# MotionerController.net
KiCad netlist of a schematic drawn in EAGLE
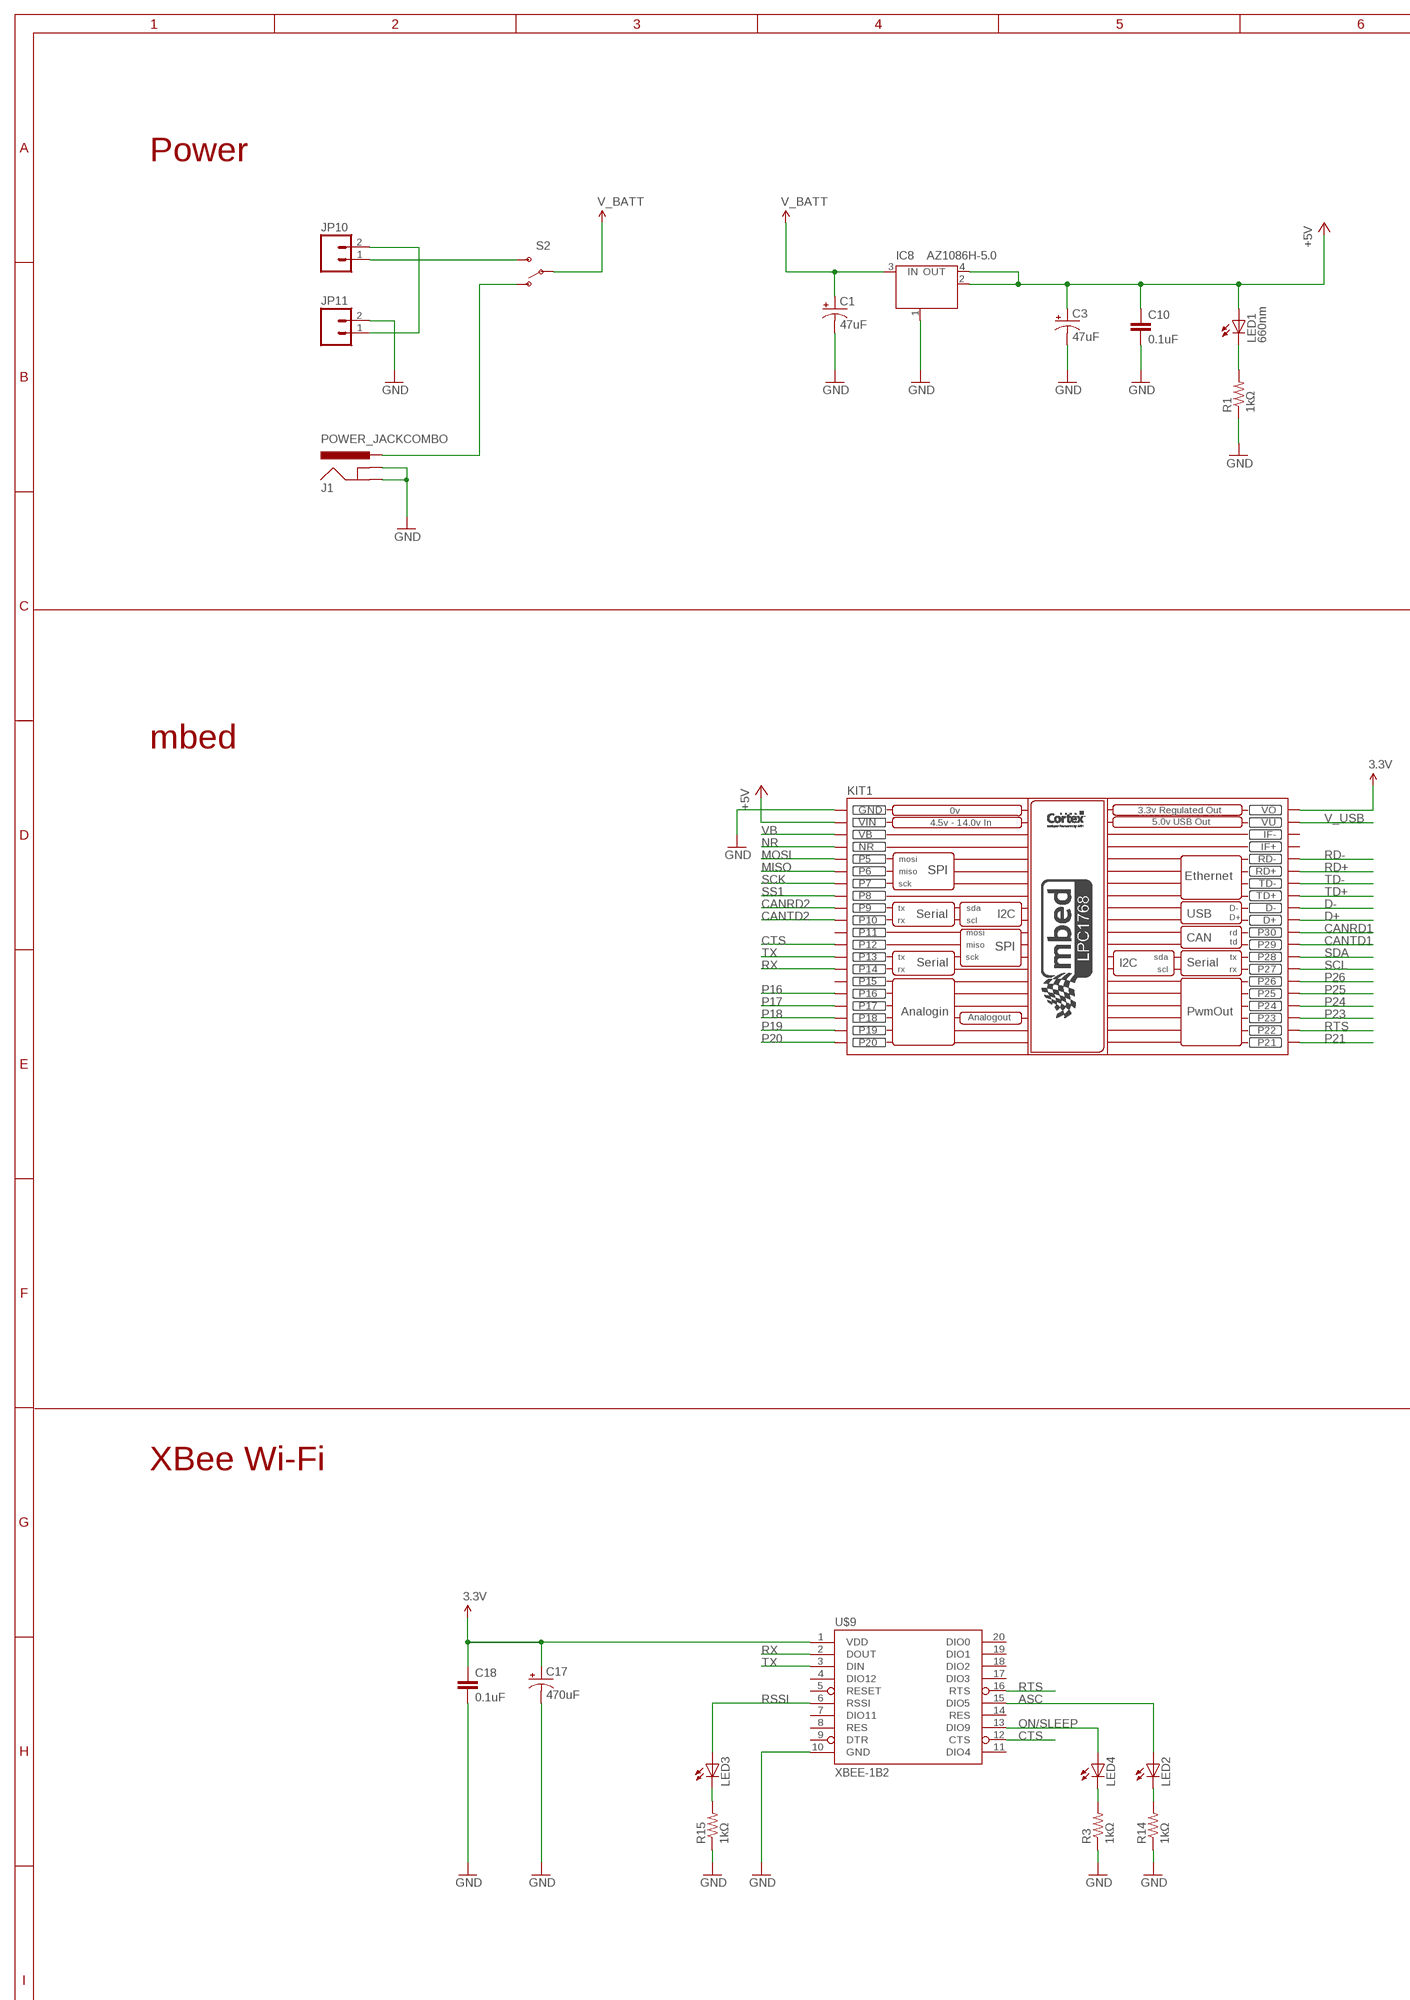
[diagram p0: schematic, sheet 1, part 1 of 2]
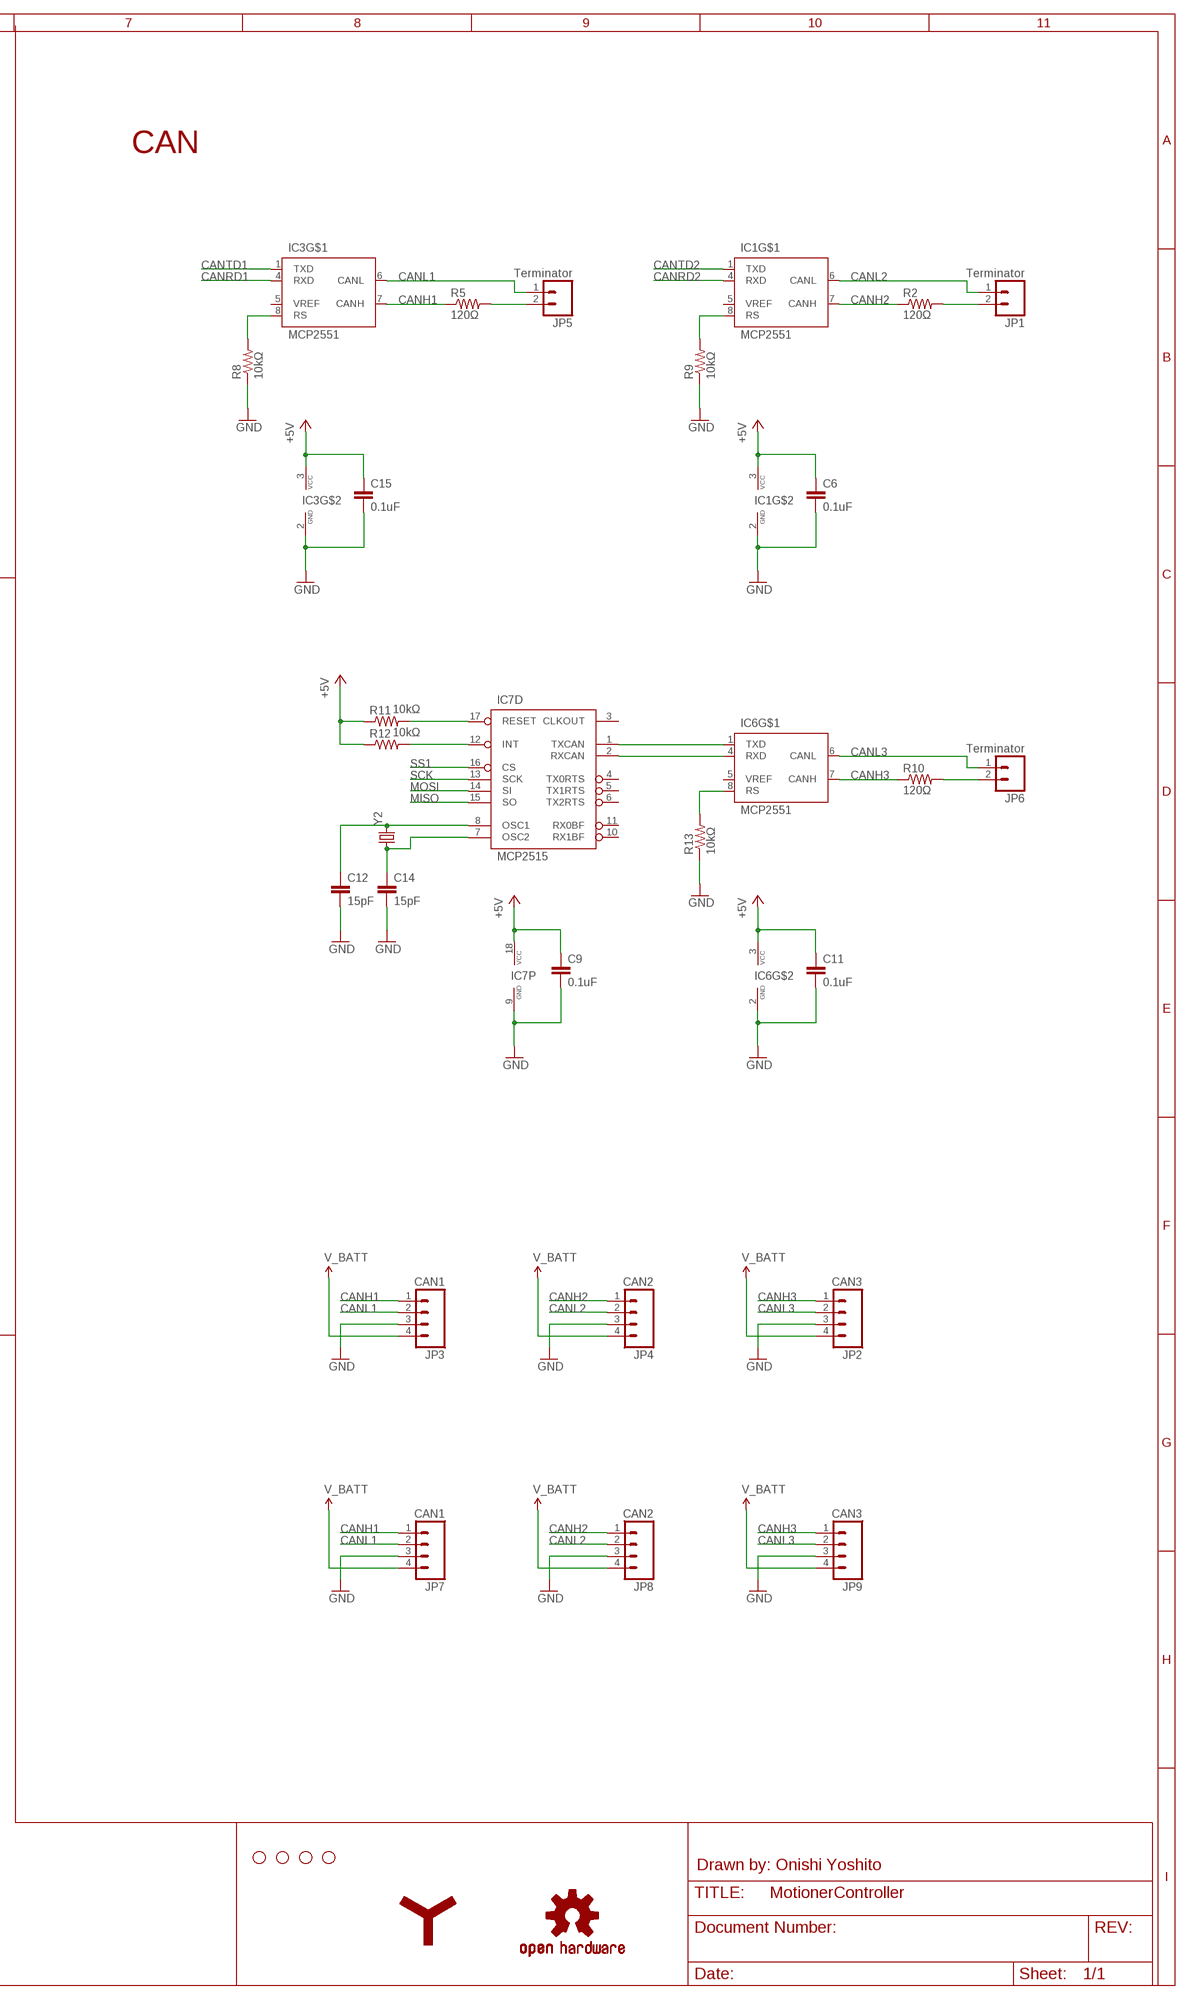
[diagram p1: schematic, sheet 1, part 2 of 2]

(export (version "E")
  (design (tool "Eeschema 10.0.6"))
  (components
    (comp (ref "C1")
      (value "47uF")
      (footprint "eagle-import:PANASONIC_D")
      (libsource (lib "eagle-import") (part "CAP_POLD"))
    )
    (comp (ref "C3")
      (value "47uF")
      (footprint "eagle-import:PANASONIC_D")
      (libsource (lib "eagle-import") (part "CAP_POLD"))
    )
    (comp (ref "C6")
      (value "0.1uF")
      (footprint "eagle-import:0603-CAP")
      (libsource (lib "eagle-import") (part "CAP0603-CAP"))
    )
    (comp (ref "C9")
      (value "0.1uF")
      (footprint "eagle-import:0603-CAP")
      (libsource (lib "eagle-import") (part "CAP0603-CAP"))
    )
    (comp (ref "C10")
      (value "0.1uF")
      (footprint "eagle-import:0603-CAP")
      (libsource (lib "eagle-import") (part "CAP0603-CAP"))
    )
    (comp (ref "C11")
      (value "0.1uF")
      (footprint "eagle-import:0603-CAP")
      (libsource (lib "eagle-import") (part "CAP0603-CAP"))
    )
    (comp (ref "C12")
      (value "15pF")
      (footprint "eagle-import:0603-CAP")
      (libsource (lib "eagle-import") (part "CAP0603-CAP"))
    )
    (comp (ref "C14")
      (value "15pF")
      (footprint "eagle-import:0603-CAP")
      (libsource (lib "eagle-import") (part "CAP0603-CAP"))
    )
    (comp (ref "C15")
      (value "0.1uF")
      (footprint "eagle-import:0603-CAP")
      (libsource (lib "eagle-import") (part "CAP0603-CAP"))
    )
    (comp (ref "C17")
      (value "470uF")
      (footprint "eagle-import:PANASONIC_G")
      (libsource (lib "eagle-import") (part "CAP_POLG"))
    )
    (comp (ref "C18")
      (value "0.1uF")
      (footprint "eagle-import:0603-CAP")
      (libsource (lib "eagle-import") (part "CAP0603-CAP"))
    )
    (comp (ref "IC1")
      (value "MCP2551")
      (footprint "eagle-import:SO08")
      (libsource (lib "eagle-import") (part "MCP2551SO8"))
    )
    (comp (ref "IC3")
      (value "MCP2551")
      (footprint "eagle-import:SO08")
      (libsource (lib "eagle-import") (part "MCP2551SO8"))
    )
    (comp (ref "IC6")
      (value "MCP2551")
      (footprint "eagle-import:SO08")
      (libsource (lib "eagle-import") (part "MCP2551SO8"))
    )
    (comp (ref "IC7")
      (value "MCP2515")
      (footprint "eagle-import:SO-18W")
      (libsource (lib "eagle-import") (part "MCP2515SO"))
    )
    (comp (ref "IC8")
      (value "AZ1086H-5.0")
      (footprint "eagle-import:SOT223")
      (libsource (lib "eagle-import") (part "MC33269ST-3.3T3"))
    )
    (comp (ref "J1")
      (value "POWER_JACKCOMBO")
      (footprint "eagle-import:POWER_JACK_COMBO")
      (libsource (lib "eagle-import") (part "POWER_JACKCOMBO"))
    )
    (comp (ref "JP1")
      (value "Terminator")
      (footprint "eagle-import:1X02")
      (libsource (lib "eagle-import") (part "M02PTH"))
    )
    (comp (ref "JP2")
      (value "CAN3")
      (footprint "eagle-import:JST-4-PTH")
      (libsource (lib "eagle-import") (part "M04JST-PTH"))
    )
    (comp (ref "JP3")
      (value "CAN1")
      (footprint "eagle-import:JST-4-PTH")
      (libsource (lib "eagle-import") (part "M04JST-PTH"))
    )
    (comp (ref "JP4")
      (value "CAN2")
      (footprint "eagle-import:JST-4-PTH")
      (libsource (lib "eagle-import") (part "M04JST-PTH"))
    )
    (comp (ref "JP5")
      (value "Terminator")
      (footprint "eagle-import:1X02")
      (libsource (lib "eagle-import") (part "M02PTH"))
    )
    (comp (ref "JP6")
      (value "Terminator")
      (footprint "eagle-import:1X02")
      (libsource (lib "eagle-import") (part "M02PTH"))
    )
    (comp (ref "JP7")
      (value "CAN1")
      (footprint "eagle-import:JST-4-PTH")
      (libsource (lib "eagle-import") (part "M04JST-PTH"))
    )
    (comp (ref "JP8")
      (value "CAN2")
      (footprint "eagle-import:JST-4-PTH")
      (libsource (lib "eagle-import") (part "M04JST-PTH"))
    )
    (comp (ref "JP9")
      (value "CAN3")
      (footprint "eagle-import:JST-4-PTH")
      (libsource (lib "eagle-import") (part "M04JST-PTH"))
    )
    (comp (ref "JP10")
      (value "M02JST-PTH-2")
      (footprint "eagle-import:JST-2-PTH")
      (libsource (lib "eagle-import") (part "M02JST-PTH-2"))
    )
    (comp (ref "JP11")
      (value "M02JST-PTH-2")
      (footprint "eagle-import:JST-2-PTH")
      (libsource (lib "eagle-import") (part "M02JST-PTH-2"))
    )
    (comp (ref "JP12")
      (value "STAND-OFF")
      (footprint "eagle-import:STAND-OFF")
      (libsource (lib "eagle-import") (part "STAND-OFF"))
    )
    (comp (ref "JP13")
      (value "STAND-OFF")
      (footprint "eagle-import:STAND-OFF")
      (libsource (lib "eagle-import") (part "STAND-OFF"))
    )
    (comp (ref "JP15")
      (value "STAND-OFF")
      (footprint "eagle-import:STAND-OFF")
      (libsource (lib "eagle-import") (part "STAND-OFF"))
    )
    (comp (ref "JP16")
      (value "STAND-OFF")
      (footprint "eagle-import:STAND-OFF")
      (libsource (lib "eagle-import") (part "STAND-OFF"))
    )
    (comp (ref "KIT1")
      (value "MBED_NXP_LPC1768")
      (footprint "eagle-import:MBED-KIT")
      (libsource (lib "eagle-import") (part "MBED_NXP_LPC1768"))
    )
    (comp (ref "LED1")
      (value "660nm")
      (footprint "eagle-import:LED-0603")
      (libsource (lib "eagle-import") (part "LED0603"))
    )
    (comp (ref "LED2")
      (value "LED0603")
      (footprint "eagle-import:LED-0603")
      (libsource (lib "eagle-import") (part "LED0603"))
    )
    (comp (ref "LED3")
      (value "LED0603")
      (footprint "eagle-import:LED-0603")
      (libsource (lib "eagle-import") (part "LED0603"))
    )
    (comp (ref "LED4")
      (value "LED0603")
      (footprint "eagle-import:LED-0603")
      (libsource (lib "eagle-import") (part "LED0603"))
    )
    (comp (ref "R1")
      (value "1kΩ")
      (footprint "eagle-import:0603-RES")
      (libsource (lib "eagle-import") (part "RESISTOR0603-RES"))
    )
    (comp (ref "R2")
      (value "120Ω")
      (footprint "eagle-import:0603-RES")
      (libsource (lib "eagle-import") (part "RESISTOR0603-RES"))
    )
    (comp (ref "R3")
      (value "1kΩ")
      (footprint "eagle-import:0603-RES")
      (libsource (lib "eagle-import") (part "RESISTOR0603-RES"))
    )
    (comp (ref "R5")
      (value "120Ω")
      (footprint "eagle-import:0603-RES")
      (libsource (lib "eagle-import") (part "RESISTOR0603-RES"))
    )
    (comp (ref "R8")
      (value "10kΩ")
      (footprint "eagle-import:0603-RES")
      (libsource (lib "eagle-import") (part "RESISTOR0603-RES"))
    )
    (comp (ref "R9")
      (value "10kΩ")
      (footprint "eagle-import:0603-RES")
      (libsource (lib "eagle-import") (part "RESISTOR0603-RES"))
    )
    (comp (ref "R10")
      (value "120Ω")
      (footprint "eagle-import:0603-RES")
      (libsource (lib "eagle-import") (part "RESISTOR0603-RES"))
    )
    (comp (ref "R11")
      (value "10kΩ")
      (footprint "eagle-import:0603-RES")
      (libsource (lib "eagle-import") (part "RESISTOR0603-RES"))
    )
    (comp (ref "R12")
      (value "10kΩ")
      (footprint "eagle-import:0603-RES")
      (libsource (lib "eagle-import") (part "RESISTOR0603-RES"))
    )
    (comp (ref "R13")
      (value "10kΩ")
      (footprint "eagle-import:0603-RES")
      (libsource (lib "eagle-import") (part "RESISTOR0603-RES"))
    )
    (comp (ref "R14")
      (value "1kΩ")
      (footprint "eagle-import:0603-RES")
      (libsource (lib "eagle-import") (part "RESISTOR0603-RES"))
    )
    (comp (ref "R15")
      (value "1kΩ")
      (footprint "eagle-import:0603-RES")
      (libsource (lib "eagle-import") (part "RESISTOR0603-RES"))
    )
    (comp (ref "S2")
      (value "SWITCH-SPDTPTH")
      (footprint "eagle-import:SWITCH-SPDT")
      (libsource (lib "eagle-import") (part "SWITCH-SPDTPTH"))
    )
    (comp (ref "U$9")
      (value "XBEE-1B2")
      (footprint "eagle-import:XBEE-SILK")
      (libsource (lib "eagle-import") (part "XBEE-1B2"))
    )
    (comp (ref "U$10")
      (value "YCAM_LOGO_L")
      (footprint "eagle-import:YCAM_LOGO_L")
      (libsource (lib "eagle-import") (part "YCAM_LOGO_L"))
    )
    (comp (ref "U$12")
      (value "OSHW-LOGOL")
      (footprint "eagle-import:OSHW-LOGO-L")
      (libsource (lib "eagle-import") (part "OSHW-LOGOL"))
    )
    (comp (ref "Y2")
      (value "CRYSTAL5X3")
      (footprint "eagle-import:CRYSTAL-SMD-5X3")
      (libsource (lib "eagle-import") (part "CRYSTAL5X3"))
    )
  )
  (nets
    (net (code "1") (name "+5V") (class "Default")
      (node (ref "C10") (pin "1") (pinfunction "1_1") (pintype "passive"))
      (node (ref "C11") (pin "1") (pinfunction "1_1") (pintype "passive"))
      (node (ref "C15") (pin "1") (pinfunction "1_1") (pintype "passive"))
      (node (ref "C3") (pin "+") (pinfunction "+_+") (pintype "passive"))
      (node (ref "C6") (pin "1") (pinfunction "1_1") (pintype "passive"))
      (node (ref "C9") (pin "1") (pinfunction "1_1") (pintype "passive"))
      (node (ref "IC1") (pin "3") (pinfunction "VCC_3") (pintype "power_in"))
      (node (ref "IC3") (pin "3") (pinfunction "VCC_3") (pintype "power_in"))
      (node (ref "IC6") (pin "3") (pinfunction "VCC_3") (pintype "power_in"))
      (node (ref "IC7") (pin "18") (pinfunction "VCC_18") (pintype "power_in"))
      (node (ref "IC8") (pin "2") (pinfunction "OUT_2") (pintype "passive"))
      (node (ref "IC8") (pin "4") (pinfunction "OUT_4") (pintype "passive"))
      (node (ref "KIT1") (pin "VIN") (pinfunction "VIN_VIN") (pintype "power_in"))
      (node (ref "LED1") (pin "A") (pinfunction "A_A") (pintype "passive"))
      (node (ref "R11") (pin "1") (pinfunction "1_1") (pintype "passive"))
      (node (ref "R12") (pin "1") (pinfunction "1_1") (pintype "passive"))
    )
    (net (code "2") (name "/ASC") (class "Default")
      (node (ref "LED2") (pin "A") (pinfunction "A_A") (pintype "passive"))
      (node (ref "U$9") (pin "15") (pinfunction "DIO5_15") (pintype "bidirectional"))
    )
    (net (code "3") (name "/CANH1") (class "Default")
      (node (ref "IC3") (pin "7") (pinfunction "CANH_7") (pintype "bidirectional"))
      (node (ref "JP3") (pin "1") (pinfunction "1_1") (pintype "passive"))
      (node (ref "JP7") (pin "1") (pinfunction "1_1") (pintype "passive"))
      (node (ref "R5") (pin "1") (pinfunction "1_1") (pintype "passive"))
    )
    (net (code "4") (name "/CANH2") (class "Default")
      (node (ref "IC1") (pin "7") (pinfunction "CANH_7") (pintype "bidirectional"))
      (node (ref "JP4") (pin "1") (pinfunction "1_1") (pintype "passive"))
      (node (ref "JP8") (pin "1") (pinfunction "1_1") (pintype "passive"))
      (node (ref "R2") (pin "1") (pinfunction "1_1") (pintype "passive"))
    )
    (net (code "5") (name "/CANH3") (class "Default")
      (node (ref "IC6") (pin "7") (pinfunction "CANH_7") (pintype "bidirectional"))
      (node (ref "JP2") (pin "1") (pinfunction "1_1") (pintype "passive"))
      (node (ref "JP9") (pin "1") (pinfunction "1_1") (pintype "passive"))
      (node (ref "R10") (pin "1") (pinfunction "1_1") (pintype "passive"))
    )
    (net (code "6") (name "/CANL1") (class "Default")
      (node (ref "IC3") (pin "6") (pinfunction "CANL_6") (pintype "bidirectional"))
      (node (ref "JP3") (pin "2") (pinfunction "2_2") (pintype "passive"))
      (node (ref "JP5") (pin "1") (pinfunction "1_1") (pintype "passive"))
      (node (ref "JP7") (pin "2") (pinfunction "2_2") (pintype "passive"))
    )
    (net (code "7") (name "/CANL2") (class "Default")
      (node (ref "IC1") (pin "6") (pinfunction "CANL_6") (pintype "bidirectional"))
      (node (ref "JP1") (pin "1") (pinfunction "1_1") (pintype "passive"))
      (node (ref "JP4") (pin "2") (pinfunction "2_2") (pintype "passive"))
      (node (ref "JP8") (pin "2") (pinfunction "2_2") (pintype "passive"))
    )
    (net (code "8") (name "/CANL3") (class "Default")
      (node (ref "IC6") (pin "6") (pinfunction "CANL_6") (pintype "bidirectional"))
      (node (ref "JP2") (pin "2") (pinfunction "2_2") (pintype "passive"))
      (node (ref "JP6") (pin "1") (pinfunction "1_1") (pintype "passive"))
      (node (ref "JP9") (pin "2") (pinfunction "2_2") (pintype "passive"))
    )
    (net (code "9") (name "/CANRD1") (class "Default")
      (node (ref "IC3") (pin "4") (pinfunction "RXD_4") (pintype "bidirectional"))
      (node (ref "KIT1") (pin "P$30") (pinfunction "P30_P$30") (pintype "bidirectional"))
    )
    (net (code "10") (name "/CANRD2") (class "Default")
      (node (ref "IC1") (pin "4") (pinfunction "RXD_4") (pintype "bidirectional"))
      (node (ref "KIT1") (pin "P$9") (pinfunction "P9_P$9") (pintype "bidirectional"))
    )
    (net (code "11") (name "/CANTD1") (class "Default")
      (node (ref "IC3") (pin "1") (pinfunction "TXD_1") (pintype "bidirectional"))
      (node (ref "KIT1") (pin "P$29") (pinfunction "P29_P$29") (pintype "bidirectional"))
    )
    (net (code "12") (name "/CANTD2") (class "Default")
      (node (ref "IC1") (pin "1") (pinfunction "TXD_1") (pintype "bidirectional"))
      (node (ref "KIT1") (pin "P$10") (pinfunction "P10_P$10") (pintype "bidirectional"))
    )
    (net (code "13") (name "/CTS") (class "Default")
      (node (ref "KIT1") (pin "P$12") (pinfunction "P12_P$12") (pintype "bidirectional"))
      (node (ref "U$9") (pin "12") (pinfunction "CTS_12") (pintype "output"))
    )
    (net (code "14") (name "/D+") (class "Default")
      (node (ref "KIT1") (pin "D+") (pinfunction "D+_D+") (pintype "bidirectional"))
    )
    (net (code "15") (name "/D-") (class "Default")
      (node (ref "KIT1") (pin "D-") (pinfunction "D-_D-") (pintype "bidirectional"))
    )
    (net (code "16") (name "/MISO") (class "Default")
      (node (ref "IC7") (pin "15") (pinfunction "SO_15") (pintype "output"))
      (node (ref "KIT1") (pin "P$6") (pinfunction "P6_P$6") (pintype "bidirectional"))
    )
    (net (code "17") (name "/MOSI") (class "Default")
      (node (ref "IC7") (pin "14") (pinfunction "SI_14") (pintype "input"))
      (node (ref "KIT1") (pin "P$5") (pinfunction "P5_P$5") (pintype "bidirectional"))
    )
    (net (code "18") (name "/NR") (class "Default")
      (node (ref "KIT1") (pin "NR") (pinfunction "NR_NR") (pintype "power_in"))
    )
    (net (code "19") (name "/ON{slash}SLEEP") (class "Default")
      (node (ref "LED4") (pin "A") (pinfunction "A_A") (pintype "passive"))
      (node (ref "U$9") (pin "13") (pinfunction "DIO9_13") (pintype "bidirectional"))
    )
    (net (code "20") (name "/P16") (class "Default")
      (node (ref "KIT1") (pin "P$16") (pinfunction "P16_P$16") (pintype "bidirectional"))
    )
    (net (code "21") (name "/P17") (class "Default")
      (node (ref "KIT1") (pin "P$17") (pinfunction "P17_P$17") (pintype "bidirectional"))
    )
    (net (code "22") (name "/P18") (class "Default")
      (node (ref "KIT1") (pin "P$18") (pinfunction "P18_P$18") (pintype "bidirectional"))
    )
    (net (code "23") (name "/P19") (class "Default")
      (node (ref "KIT1") (pin "P$19") (pinfunction "P19_P$19") (pintype "bidirectional"))
    )
    (net (code "24") (name "/P20") (class "Default")
      (node (ref "KIT1") (pin "P$20") (pinfunction "P20_P$20") (pintype "bidirectional"))
    )
    (net (code "25") (name "/P21") (class "Default")
      (node (ref "KIT1") (pin "P$21") (pinfunction "P21_P$21") (pintype "bidirectional"))
    )
    (net (code "26") (name "/P23") (class "Default")
      (node (ref "KIT1") (pin "P$23") (pinfunction "P23_P$23") (pintype "bidirectional"))
    )
    (net (code "27") (name "/P24") (class "Default")
      (node (ref "KIT1") (pin "P$24") (pinfunction "P24_P$24") (pintype "bidirectional"))
    )
    (net (code "28") (name "/P25") (class "Default")
      (node (ref "KIT1") (pin "P$25") (pinfunction "P25_P$25") (pintype "bidirectional"))
    )
    (net (code "29") (name "/P26") (class "Default")
      (node (ref "KIT1") (pin "P$26") (pinfunction "P26_P$26") (pintype "bidirectional"))
    )
    (net (code "30") (name "/RD+") (class "Default")
      (node (ref "KIT1") (pin "RD+") (pinfunction "RD+_RD+") (pintype "bidirectional"))
    )
    (net (code "31") (name "/RD-") (class "Default")
      (node (ref "KIT1") (pin "RD-") (pinfunction "RD-_RD-") (pintype "bidirectional"))
    )
    (net (code "32") (name "/RSSI") (class "Default")
      (node (ref "LED3") (pin "A") (pinfunction "A_A") (pintype "passive"))
      (node (ref "U$9") (pin "6") (pinfunction "RSSI_6") (pintype "bidirectional"))
    )
    (net (code "33") (name "/RTS") (class "Default")
      (node (ref "KIT1") (pin "P$22") (pinfunction "P22_P$22") (pintype "bidirectional"))
      (node (ref "U$9") (pin "16") (pinfunction "RTS_16") (pintype "input"))
    )
    (net (code "34") (name "/RX") (class "Default")
      (node (ref "KIT1") (pin "P$14") (pinfunction "P14_P$14") (pintype "bidirectional"))
      (node (ref "U$9") (pin "2") (pinfunction "DOUT_2") (pintype "output"))
    )
    (net (code "35") (name "/SCK") (class "Default")
      (node (ref "IC7") (pin "13") (pinfunction "SCK_13") (pintype "input"))
      (node (ref "KIT1") (pin "P$7") (pinfunction "P7_P$7") (pintype "bidirectional"))
    )
    (net (code "36") (name "/SCL") (class "Default")
      (node (ref "KIT1") (pin "P$27") (pinfunction "P27_P$27") (pintype "bidirectional"))
    )
    (net (code "37") (name "/SDA") (class "Default")
      (node (ref "KIT1") (pin "P$28") (pinfunction "P28_P$28") (pintype "bidirectional"))
    )
    (net (code "38") (name "/SS1") (class "Default")
      (node (ref "IC7") (pin "16") (pinfunction "CS_16") (pintype "input"))
      (node (ref "KIT1") (pin "P$8") (pinfunction "P8_P$8") (pintype "bidirectional"))
    )
    (net (code "39") (name "/TD+") (class "Default")
      (node (ref "KIT1") (pin "TD+") (pinfunction "TD+_TD+") (pintype "bidirectional"))
    )
    (net (code "40") (name "/TD-") (class "Default")
      (node (ref "KIT1") (pin "TD-") (pinfunction "TD-_TD-") (pintype "bidirectional"))
    )
    (net (code "41") (name "/TX") (class "Default")
      (node (ref "KIT1") (pin "P$13") (pinfunction "P13_P$13") (pintype "bidirectional"))
      (node (ref "U$9") (pin "3") (pinfunction "DIN_3") (pintype "input"))
    )
    (net (code "42") (name "/VB") (class "Default")
      (node (ref "KIT1") (pin "VB") (pinfunction "VB_VB") (pintype "power_in"))
    )
    (net (code "43") (name "/V_USB") (class "Default")
      (node (ref "KIT1") (pin "VU") (pinfunction "VU_VU") (pintype "power_in"))
    )
    (net (code "44") (name "3.3V") (class "Default")
      (node (ref "C17") (pin "+") (pinfunction "+_+") (pintype "passive"))
      (node (ref "C18") (pin "1") (pinfunction "1_1") (pintype "passive"))
      (node (ref "KIT1") (pin "VOUT") (pinfunction "VO_VOUT") (pintype "power_in"))
      (node (ref "U$9") (pin "1") (pinfunction "VDD_1") (pintype "power_in"))
    )
    (net (code "45") (name "GND") (class "Default")
      (node (ref "C1") (pin "-") (pinfunction "-_-") (pintype "passive"))
      (node (ref "C10") (pin "2") (pinfunction "2_2") (pintype "passive"))
      (node (ref "C11") (pin "2") (pinfunction "2_2") (pintype "passive"))
      (node (ref "C12") (pin "2") (pinfunction "2_2") (pintype "passive"))
      (node (ref "C14") (pin "2") (pinfunction "2_2") (pintype "passive"))
      (node (ref "C15") (pin "2") (pinfunction "2_2") (pintype "passive"))
      (node (ref "C17") (pin "-") (pinfunction "-_-") (pintype "passive"))
      (node (ref "C18") (pin "2") (pinfunction "2_2") (pintype "passive"))
      (node (ref "C3") (pin "-") (pinfunction "-_-") (pintype "passive"))
      (node (ref "C6") (pin "2") (pinfunction "2_2") (pintype "passive"))
      (node (ref "C9") (pin "2") (pinfunction "2_2") (pintype "passive"))
      (node (ref "IC1") (pin "2") (pinfunction "GND_2") (pintype "power_in"))
      (node (ref "IC3") (pin "2") (pinfunction "GND_2") (pintype "power_in"))
      (node (ref "IC6") (pin "2") (pinfunction "GND_2") (pintype "power_in"))
      (node (ref "IC7") (pin "9") (pinfunction "GND_9") (pintype "power_in"))
      (node (ref "IC8") (pin "1") (pinfunction "GND/ADJ_1") (pintype "input"))
      (node (ref "J1") (pin "GND") (pinfunction "GNDBREAK_GND") (pintype "bidirectional"))
      (node (ref "J1") (pin "GND@1") (pinfunction "GND_GND@1") (pintype "bidirectional"))
      (node (ref "JP11") (pin "2") (pinfunction "2_2") (pintype "passive"))
      (node (ref "JP2") (pin "3") (pinfunction "3_3") (pintype "passive"))
      (node (ref "JP3") (pin "3") (pinfunction "3_3") (pintype "passive"))
      (node (ref "JP4") (pin "3") (pinfunction "3_3") (pintype "passive"))
      (node (ref "JP7") (pin "3") (pinfunction "3_3") (pintype "passive"))
      (node (ref "JP8") (pin "3") (pinfunction "3_3") (pintype "passive"))
      (node (ref "JP9") (pin "3") (pinfunction "3_3") (pintype "passive"))
      (node (ref "KIT1") (pin "GND") (pinfunction "GND_GND") (pintype "power_in"))
      (node (ref "R1") (pin "1") (pinfunction "1_1") (pintype "passive"))
      (node (ref "R13") (pin "1") (pinfunction "1_1") (pintype "passive"))
      (node (ref "R14") (pin "1") (pinfunction "1_1") (pintype "passive"))
      (node (ref "R15") (pin "1") (pinfunction "1_1") (pintype "passive"))
      (node (ref "R3") (pin "1") (pinfunction "1_1") (pintype "passive"))
      (node (ref "R8") (pin "1") (pinfunction "1_1") (pintype "passive"))
      (node (ref "R9") (pin "1") (pinfunction "1_1") (pintype "passive"))
      (node (ref "U$9") (pin "10") (pinfunction "GND_10") (pintype "power_in"))
    )
    (net (code "46") (name "Net-(IC1A-RS)") (class "Default")
      (node (ref "IC1") (pin "8") (pinfunction "RS_8") (pintype "bidirectional"))
      (node (ref "R9") (pin "2") (pinfunction "2_2") (pintype "passive"))
    )
    (net (code "47") (name "Net-(IC3A-RS)") (class "Default")
      (node (ref "IC3") (pin "8") (pinfunction "RS_8") (pintype "bidirectional"))
      (node (ref "R8") (pin "2") (pinfunction "2_2") (pintype "passive"))
    )
    (net (code "48") (name "Net-(IC6A-RS)") (class "Default")
      (node (ref "IC6") (pin "8") (pinfunction "RS_8") (pintype "bidirectional"))
      (node (ref "R13") (pin "2") (pinfunction "2_2") (pintype "passive"))
    )
    (net (code "49") (name "Net-(IC6A-RXD)") (class "Default")
      (node (ref "IC6") (pin "4") (pinfunction "RXD_4") (pintype "bidirectional"))
      (node (ref "IC7") (pin "2") (pinfunction "RXCAN_2") (pintype "input"))
    )
    (net (code "50") (name "Net-(IC6A-TXD)") (class "Default")
      (node (ref "IC6") (pin "1") (pinfunction "TXD_1") (pintype "bidirectional"))
      (node (ref "IC7") (pin "1") (pinfunction "TXCAN_1") (pintype "output"))
    )
    (net (code "51") (name "Net-(IC7A-INT)") (class "Default")
      (node (ref "IC7") (pin "12") (pinfunction "INT_12") (pintype "output"))
      (node (ref "R12") (pin "2") (pinfunction "2_2") (pintype "passive"))
    )
    (net (code "52") (name "Net-(IC7A-OSC1)") (class "Default")
      (node (ref "C12") (pin "1") (pinfunction "1_1") (pintype "passive"))
      (node (ref "IC7") (pin "8") (pinfunction "OSC1_8") (pintype "input"))
      (node (ref "Y2") (pin "3") (pinfunction "2_3") (pintype "passive"))
    )
    (net (code "53") (name "Net-(IC7A-OSC2)") (class "Default")
      (node (ref "C14") (pin "1") (pinfunction "1_1") (pintype "passive"))
      (node (ref "IC7") (pin "7") (pinfunction "OSC2_7") (pintype "input"))
      (node (ref "Y2") (pin "1") (pinfunction "1_1") (pintype "passive"))
    )
    (net (code "54") (name "Net-(IC7A-RESET)") (class "Default")
      (node (ref "IC7") (pin "17") (pinfunction "RESET_17") (pintype "input"))
      (node (ref "R11") (pin "2") (pinfunction "2_2") (pintype "passive"))
    )
    (net (code "55") (name "Net-(J1-PWR)") (class "Default")
      (node (ref "J1") (pin "POWER") (pinfunction "PWR_POWER") (pintype "bidirectional"))
      (node (ref "S2") (pin "1") (pinfunction "O_1") (pintype "passive"))
    )
    (net (code "56") (name "Net-(JP1-Pad2)") (class "Default")
      (node (ref "JP1") (pin "2") (pinfunction "2_2") (pintype "passive"))
      (node (ref "R2") (pin "2") (pinfunction "2_2") (pintype "passive"))
    )
    (net (code "57") (name "Net-(JP5-Pad2)") (class "Default")
      (node (ref "JP5") (pin "2") (pinfunction "2_2") (pintype "passive"))
      (node (ref "R5") (pin "2") (pinfunction "2_2") (pintype "passive"))
    )
    (net (code "58") (name "Net-(JP6-Pad2)") (class "Default")
      (node (ref "JP6") (pin "2") (pinfunction "2_2") (pintype "passive"))
      (node (ref "R10") (pin "2") (pinfunction "2_2") (pintype "passive"))
    )
    (net (code "59") (name "Net-(JP10-Pad2)") (class "Default")
      (node (ref "JP10") (pin "2") (pinfunction "2_2") (pintype "passive"))
      (node (ref "JP11") (pin "1") (pinfunction "1_1") (pintype "passive"))
    )
    (net (code "60") (name "Net-(LED1-PadC)") (class "Default")
      (node (ref "LED1") (pin "C") (pinfunction "C_C") (pintype "passive"))
      (node (ref "R1") (pin "2") (pinfunction "2_2") (pintype "passive"))
    )
    (net (code "61") (name "Net-(LED2-PadC)") (class "Default")
      (node (ref "LED2") (pin "C") (pinfunction "C_C") (pintype "passive"))
      (node (ref "R14") (pin "2") (pinfunction "2_2") (pintype "passive"))
    )
    (net (code "62") (name "Net-(LED3-PadC)") (class "Default")
      (node (ref "LED3") (pin "C") (pinfunction "C_C") (pintype "passive"))
      (node (ref "R15") (pin "2") (pinfunction "2_2") (pintype "passive"))
    )
    (net (code "63") (name "Net-(LED4-PadC)") (class "Default")
      (node (ref "LED4") (pin "C") (pinfunction "C_C") (pintype "passive"))
      (node (ref "R3") (pin "2") (pinfunction "2_2") (pintype "passive"))
    )
    (net (code "64") (name "Net-(S2-S)") (class "Default")
      (node (ref "JP10") (pin "1") (pinfunction "1_1") (pintype "passive"))
      (node (ref "S2") (pin "3") (pinfunction "S_3") (pintype "passive"))
    )
    (net (code "65") (name "V_BATT") (class "Default")
      (node (ref "C1") (pin "+") (pinfunction "+_+") (pintype "passive"))
      (node (ref "IC8") (pin "3") (pinfunction "IN_3") (pintype "input"))
      (node (ref "JP2") (pin "4") (pinfunction "4_4") (pintype "passive"))
      (node (ref "JP3") (pin "4") (pinfunction "4_4") (pintype "passive"))
      (node (ref "JP4") (pin "4") (pinfunction "4_4") (pintype "passive"))
      (node (ref "JP7") (pin "4") (pinfunction "4_4") (pintype "passive"))
      (node (ref "JP8") (pin "4") (pinfunction "4_4") (pintype "passive"))
      (node (ref "JP9") (pin "4") (pinfunction "4_4") (pintype "passive"))
      (node (ref "S2") (pin "2") (pinfunction "P_2") (pintype "passive"))
    )
    (net (code "66") (name "unconnected-(IC1A-VREF-Pad5)") (class "Default")
      (node (ref "IC1") (pin "5") (pinfunction "VREF_5") (pintype "bidirectional"))
    )
    (net (code "67") (name "unconnected-(IC3A-VREF-Pad5)") (class "Default")
      (node (ref "IC3") (pin "5") (pinfunction "VREF_5") (pintype "bidirectional"))
    )
    (net (code "68") (name "unconnected-(IC6A-VREF-Pad5)") (class "Default")
      (node (ref "IC6") (pin "5") (pinfunction "VREF_5") (pintype "bidirectional"))
    )
    (net (code "69") (name "unconnected-(IC7A-CLKOUT-Pad3)") (class "Default")
      (node (ref "IC7") (pin "3") (pinfunction "CLKOUT_3") (pintype "output"))
    )
    (net (code "70") (name "unconnected-(IC7A-RX0BF-Pad11)") (class "Default")
      (node (ref "IC7") (pin "11") (pinfunction "RX0BF_11") (pintype "output"))
    )
    (net (code "71") (name "unconnected-(IC7A-RX1BF-Pad10)") (class "Default")
      (node (ref "IC7") (pin "10") (pinfunction "RX1BF_10") (pintype "output"))
    )
    (net (code "72") (name "unconnected-(IC7A-TX0RTS-Pad4)") (class "Default")
      (node (ref "IC7") (pin "4") (pinfunction "TX0RTS_4") (pintype "input"))
    )
    (net (code "73") (name "unconnected-(IC7A-TX1RTS-Pad5)") (class "Default")
      (node (ref "IC7") (pin "5") (pinfunction "TX1RTS_5") (pintype "input"))
    )
    (net (code "74") (name "unconnected-(IC7A-TX2RTS-Pad6)") (class "Default")
      (node (ref "IC7") (pin "6") (pinfunction "TX2RTS_6") (pintype "input"))
    )
    (net (code "75") (name "unconnected-(KIT1-P11-PadP$11)") (class "Default")
      (node (ref "KIT1") (pin "P$11") (pinfunction "P11_P$11") (pintype "bidirectional"))
    )
    (net (code "76") (name "unconnected-(KIT1-P15-PadP$15)") (class "Default")
      (node (ref "KIT1") (pin "P$15") (pinfunction "P15_P$15") (pintype "bidirectional"))
    )
    (net (code "77") (name "unconnected-(KIT1-PadIF+)") (class "Default")
      (node (ref "KIT1") (pin "IF+") (pinfunction "IF+_IF+") (pintype "bidirectional"))
    )
    (net (code "78") (name "unconnected-(KIT1-PadIF-)") (class "Default")
      (node (ref "KIT1") (pin "IF-") (pinfunction "IF-_IF-") (pintype "bidirectional"))
    )
    (net (code "79") (name "unconnected-(U$9-DIO0-Pad20)") (class "Default")
      (node (ref "U$9") (pin "20") (pinfunction "DIO0_20") (pintype "bidirectional"))
    )
    (net (code "80") (name "unconnected-(U$9-DIO1-Pad19)") (class "Default")
      (node (ref "U$9") (pin "19") (pinfunction "DIO1_19") (pintype "bidirectional"))
    )
    (net (code "81") (name "unconnected-(U$9-DIO2-Pad18)") (class "Default")
      (node (ref "U$9") (pin "18") (pinfunction "DIO2_18") (pintype "bidirectional"))
    )
    (net (code "82") (name "unconnected-(U$9-DIO3-Pad17)") (class "Default")
      (node (ref "U$9") (pin "17") (pinfunction "DIO3_17") (pintype "bidirectional"))
    )
    (net (code "83") (name "unconnected-(U$9-DIO4-Pad11)") (class "Default")
      (node (ref "U$9") (pin "11") (pinfunction "DIO4_11") (pintype "bidirectional"))
    )
    (net (code "84") (name "unconnected-(U$9-DIO11-Pad7)") (class "Default")
      (node (ref "U$9") (pin "7") (pinfunction "DIO11_7") (pintype "bidirectional"))
    )
    (net (code "85") (name "unconnected-(U$9-DIO12-Pad4)") (class "Default")
      (node (ref "U$9") (pin "4") (pinfunction "DIO12_4") (pintype "bidirectional"))
    )
    (net (code "86") (name "unconnected-(U$9-DTR-Pad9)") (class "Default")
      (node (ref "U$9") (pin "9") (pinfunction "DTR_9") (pintype "bidirectional"))
    )
    (net (code "87") (name "unconnected-(U$9-RES-Pad8)") (class "Default")
      (node (ref "U$9") (pin "8") (pinfunction "RES_8") (pintype "bidirectional"))
    )
    (net (code "88") (name "unconnected-(U$9-RES-Pad14)") (class "Default")
      (node (ref "U$9") (pin "14") (pinfunction "RES_14") (pintype "bidirectional"))
    )
    (net (code "89") (name "unconnected-(U$9-RESET-Pad5)") (class "Default")
      (node (ref "U$9") (pin "5") (pinfunction "RESET_5") (pintype "input"))
    )
  )
)
